# mrShark_10.net
KiCad netlist of a schematic drawn in EAGLE
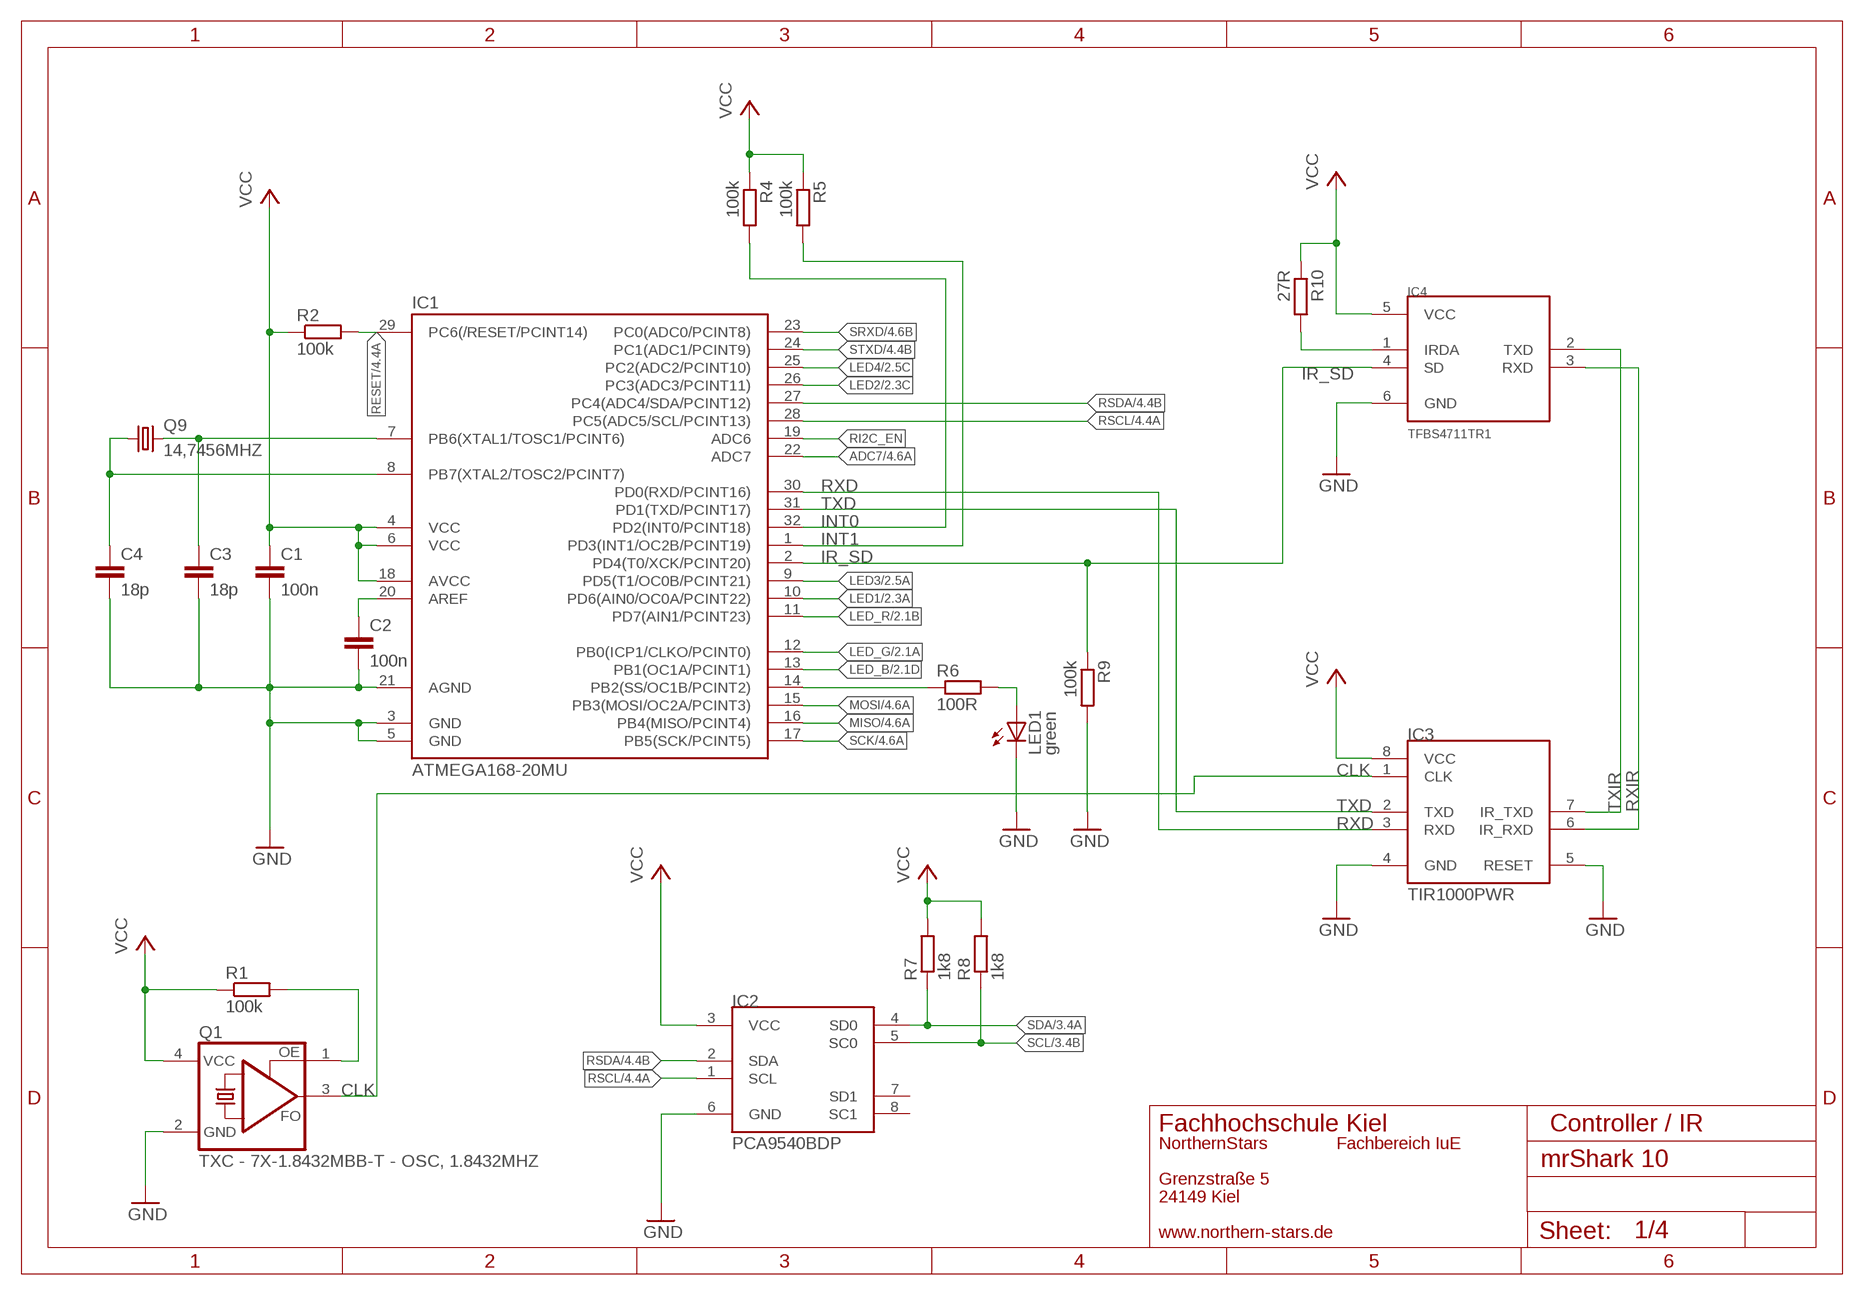
[diagram p0: schematic, sheet 1]
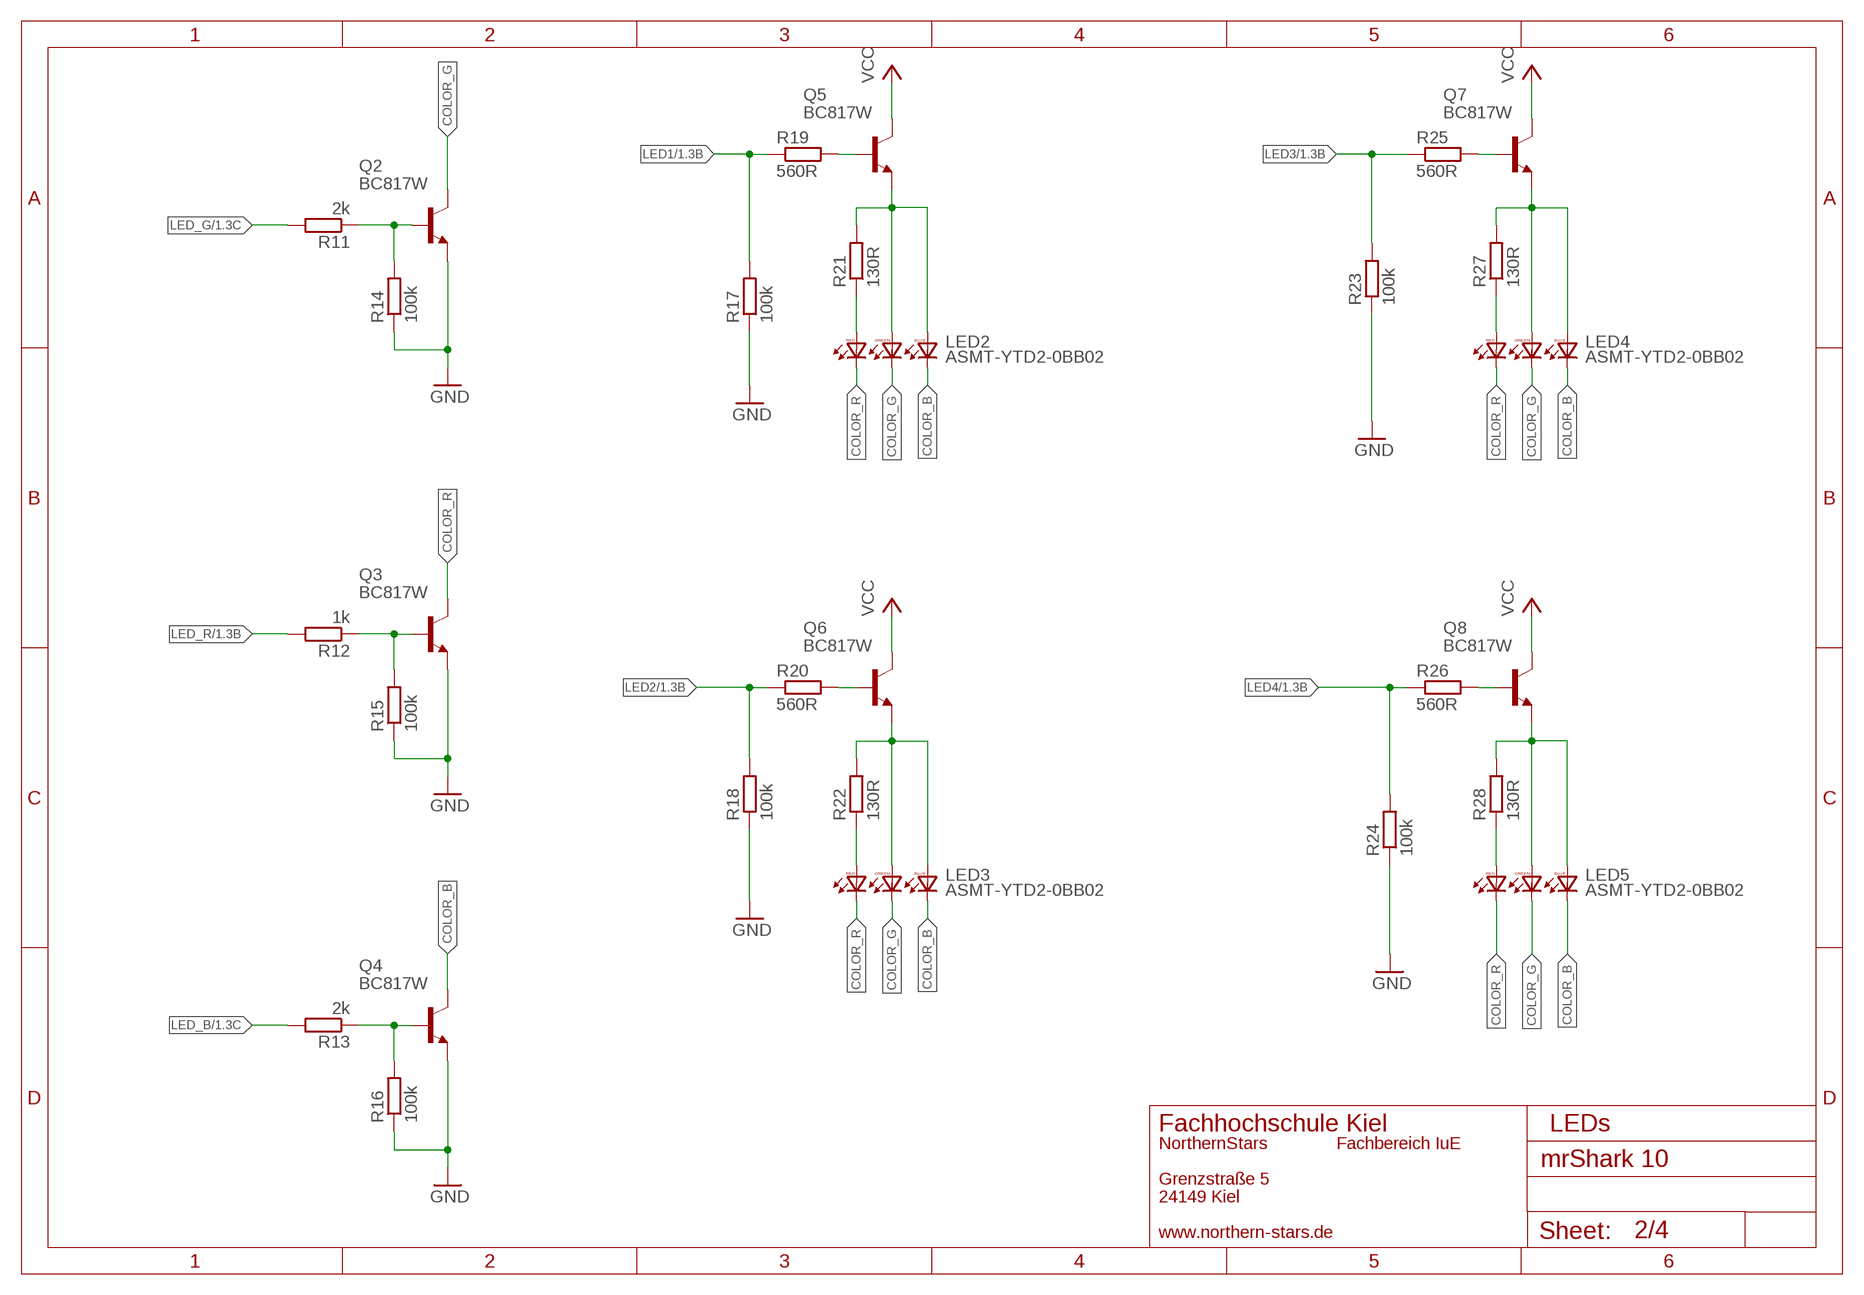
[diagram p1: schematic, sheet 2]
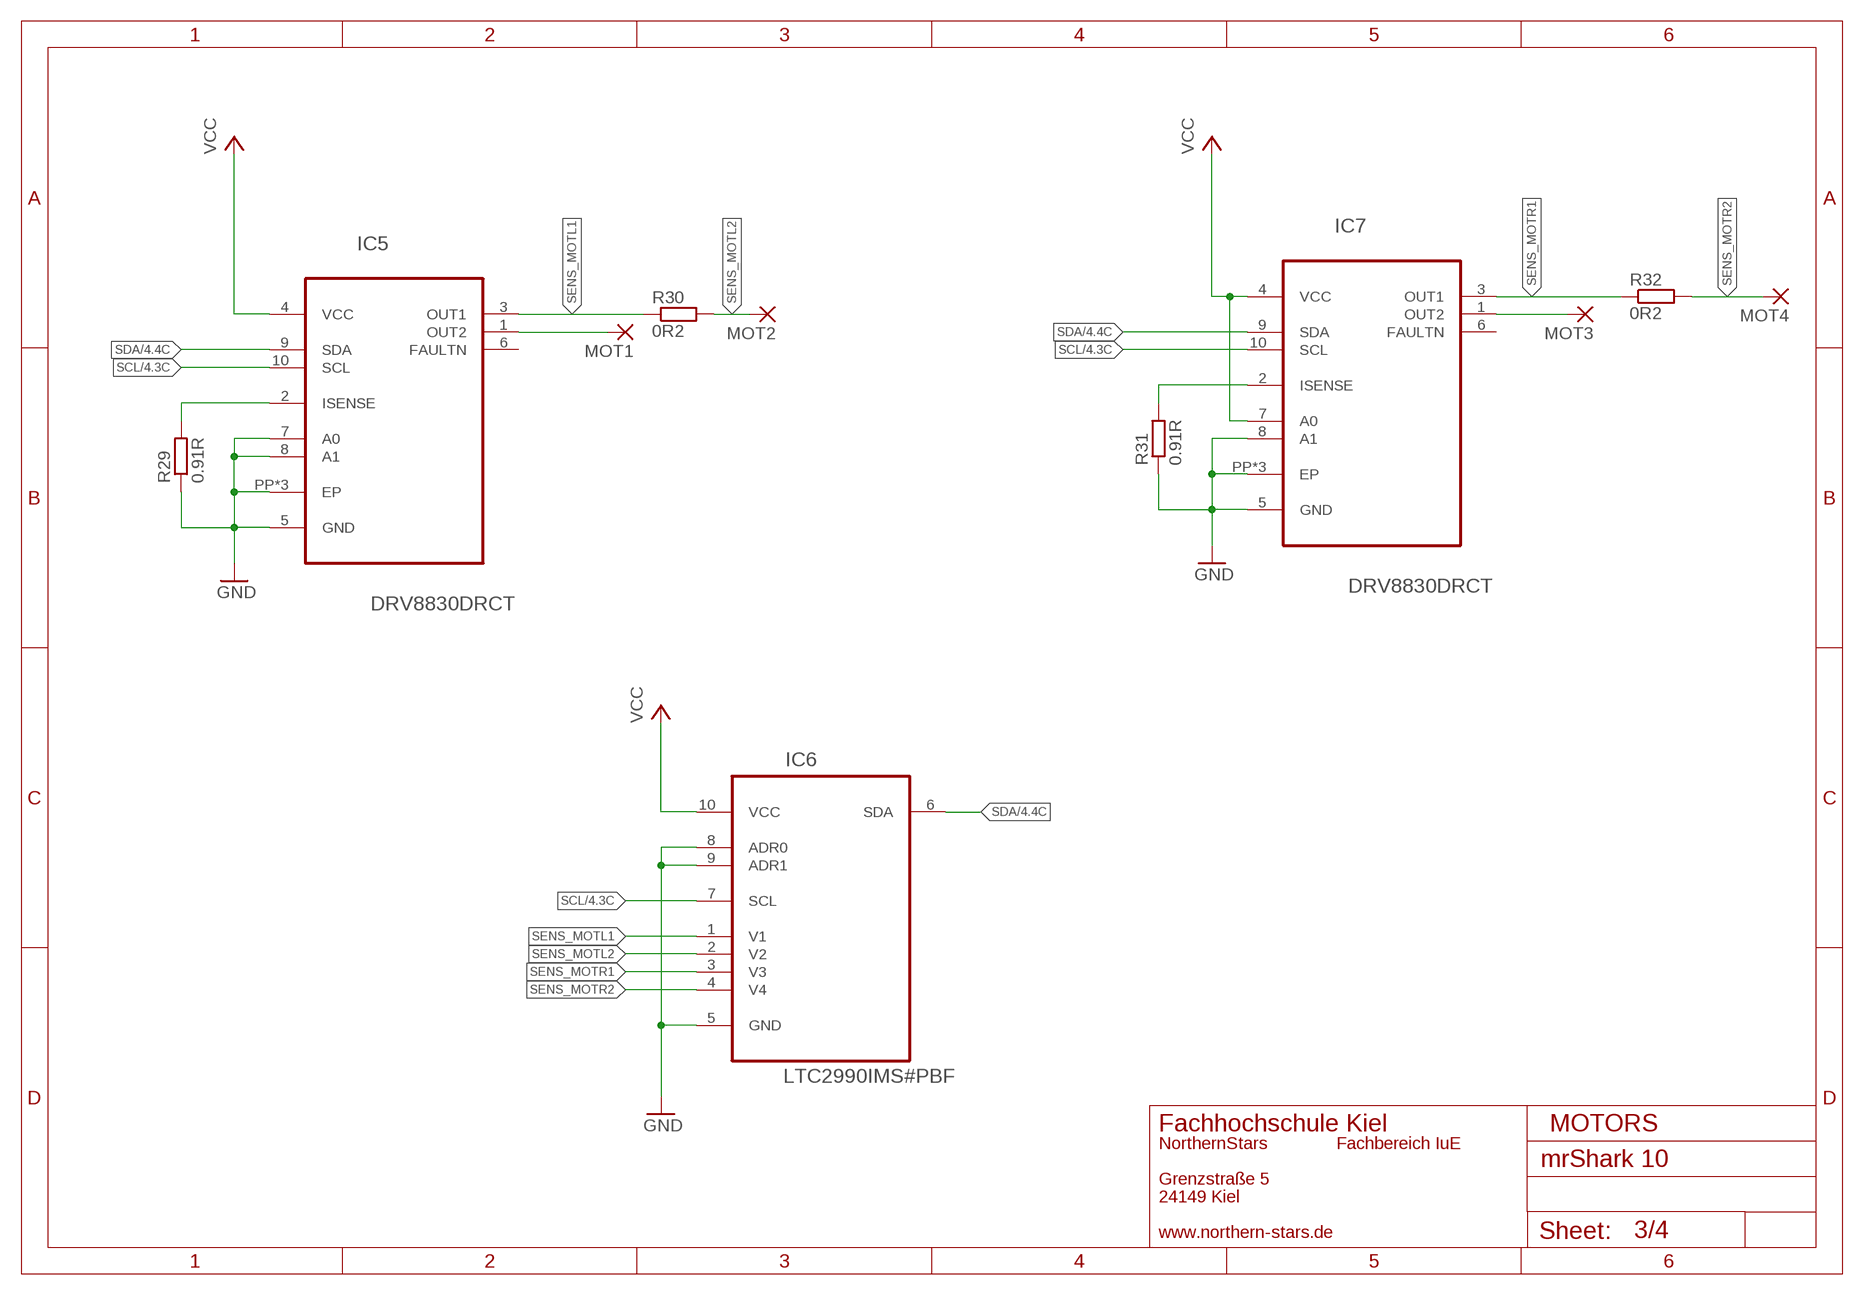
[diagram p2: schematic, sheet 3]
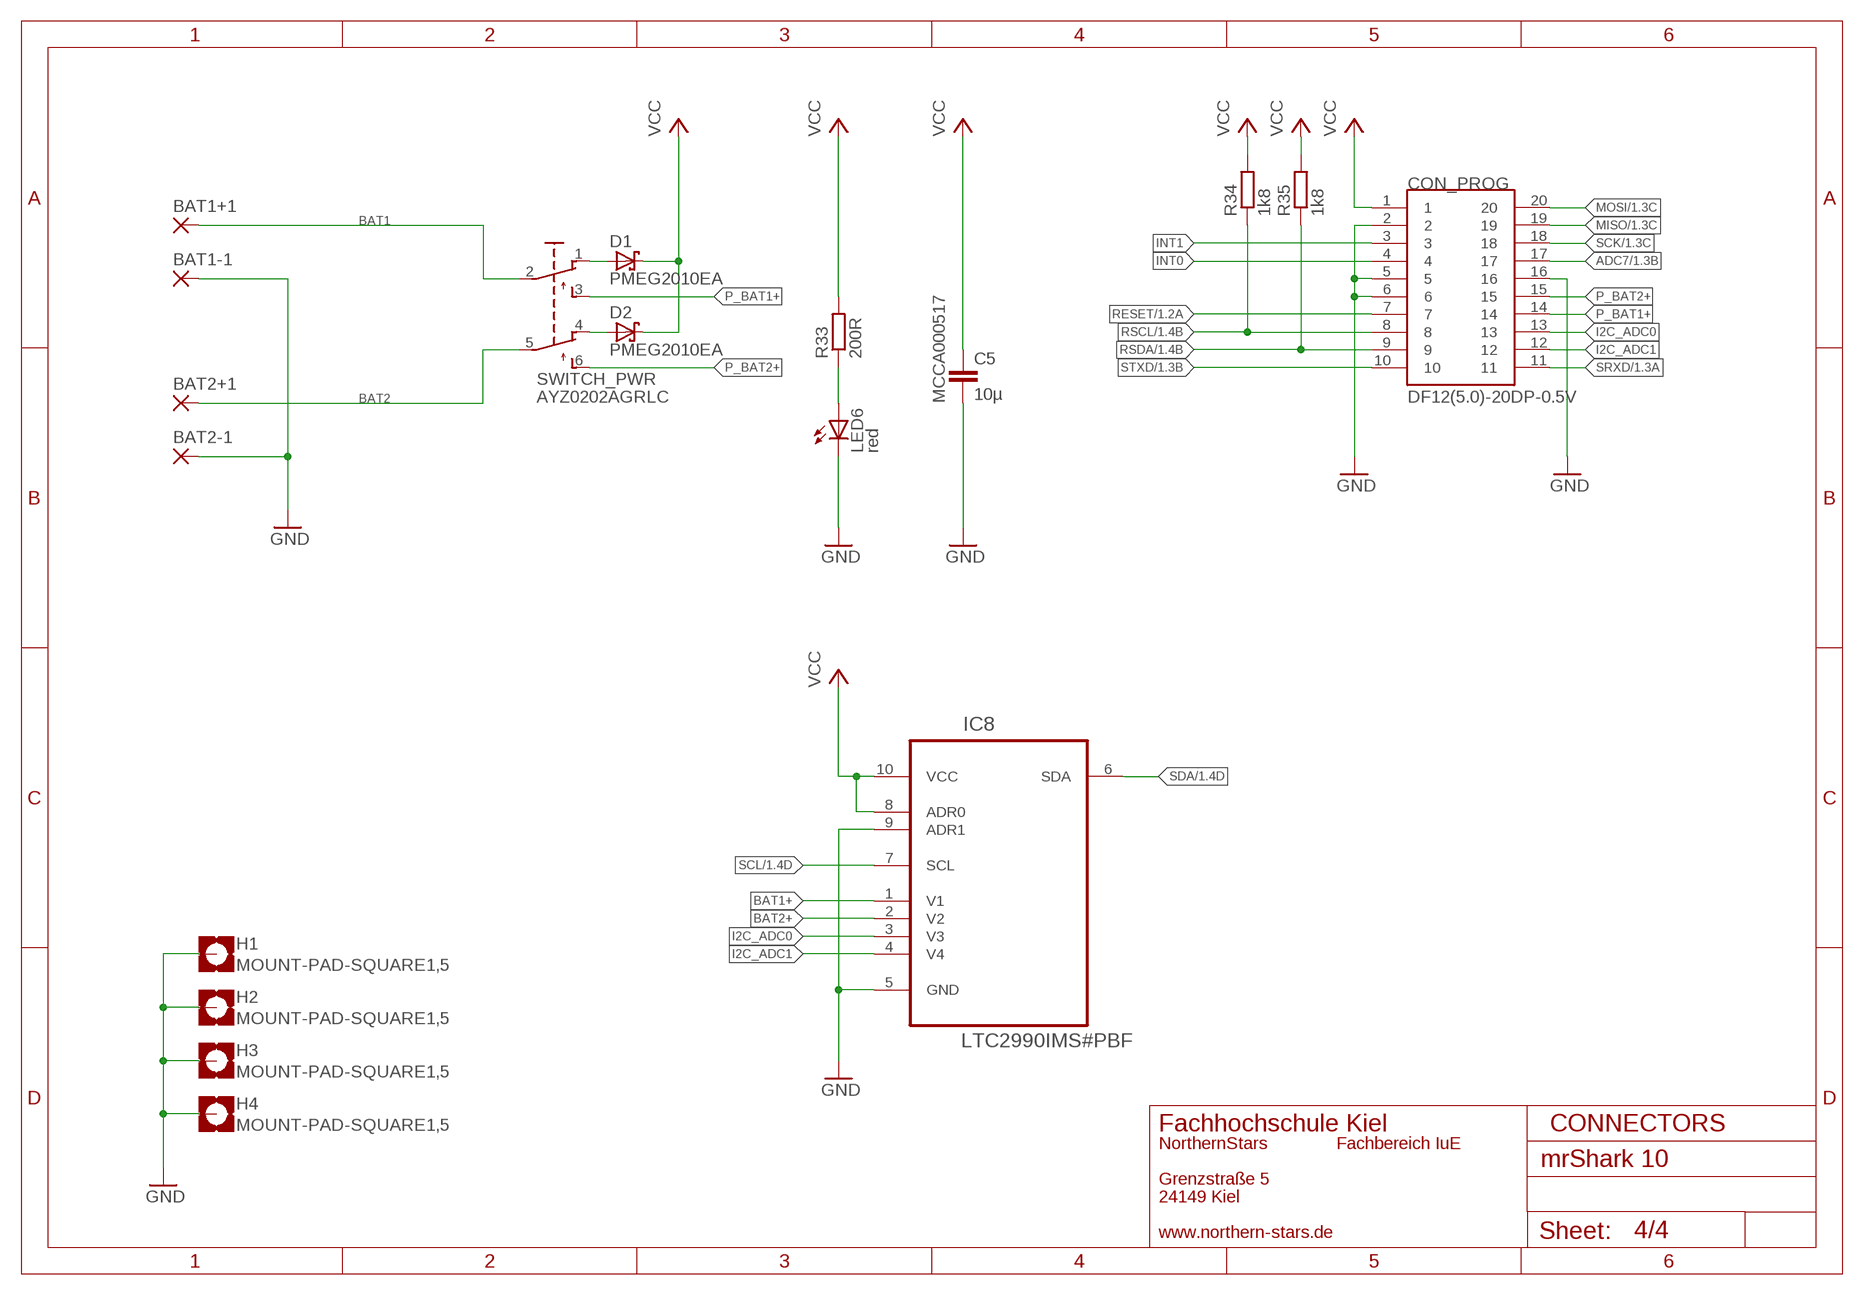
[diagram p3: schematic, sheet 4]

(export (version "E")
  (design (tool "Eeschema 10.0.6"))
  (components
    (comp (ref "C1")
      (value "100n")
      (footprint "eagle-import:C0201")
      (libsource (lib "eagle-import") (part "C-EUC0201"))
    )
    (comp (ref "C2")
      (value "100n")
      (footprint "eagle-import:C0201")
      (libsource (lib "eagle-import") (part "C-EUC0201"))
    )
    (comp (ref "C3")
      (value "18p")
      (footprint "eagle-import:C0201")
      (libsource (lib "eagle-import") (part "C-EUC0201"))
    )
    (comp (ref "C4")
      (value "18p")
      (footprint "eagle-import:C0201")
      (libsource (lib "eagle-import") (part "C-EUC0201"))
    )
    (comp (ref "IC1")
      (value "ATMEGA168-20MU")
      (footprint "eagle-import:MLF32")
      (libsource (lib "eagle-import") (part "ATMEGA48/88/168-MU"))
    )
    (comp (ref "IC2")
      (value "PCA9540BDP")
      (footprint "eagle-import:TSSOP8")
      (libsource (lib "eagle-import") (part "PCA9540TSSOP8"))
    )
    (comp (ref "IC3")
      (value "TIR1000PWR")
      (footprint "eagle-import:PW_R-PDSO-G08")
      (libsource (lib "eagle-import") (part "TIR1000PWR"))
    )
    (comp (ref "IC4")
      (value "TFBS4711TR1")
      (footprint "eagle-import:TFBS4711")
      (libsource (lib "eagle-import") (part "TFBS4711TR1"))
    )
    (comp (ref "LED1")
      (value "green")
      (footprint "eagle-import:CHIPLED_0603")
      (libsource (lib "eagle-import") (part "LEDCHIPLED_0603"))
    )
    (comp (ref "Q1")
      (value "TXC - 7X-1.8432MBB-T - OSC, 1.8432MHZ")
      (footprint "eagle-import:3.2X2.5")
      (libsource (lib "eagle-import") (part "7X-SERIES"))
    )
    (comp (ref "Q9")
      (value "14,7456MHZ")
      (footprint "eagle-import:TXC_7B_SERIES")
      (libsource (lib "eagle-import") (part "TXC-7B-SERIESSMD"))
    )
    (comp (ref "R1")
      (value "100k")
      (footprint "eagle-import:R0201")
      (libsource (lib "eagle-import") (part "R-EU_R0201"))
    )
    (comp (ref "R2")
      (value "100k")
      (footprint "eagle-import:R0201")
      (libsource (lib "eagle-import") (part "R-EU_R0201"))
    )
    (comp (ref "R4")
      (value "100k")
      (footprint "eagle-import:R0201")
      (libsource (lib "eagle-import") (part "R-EU_R0201"))
    )
    (comp (ref "R5")
      (value "100k")
      (footprint "eagle-import:R0201")
      (libsource (lib "eagle-import") (part "R-EU_R0201"))
    )
    (comp (ref "R6")
      (value "100R")
      (footprint "eagle-import:R0201")
      (libsource (lib "eagle-import") (part "R-EU_R0201"))
    )
    (comp (ref "R7")
      (value "1k8")
      (footprint "eagle-import:R0201")
      (libsource (lib "eagle-import") (part "R-EU_R0201"))
    )
    (comp (ref "R8")
      (value "1k8")
      (footprint "eagle-import:R0201")
      (libsource (lib "eagle-import") (part "R-EU_R0201"))
    )
    (comp (ref "R9")
      (value "100k")
      (footprint "eagle-import:R0201")
      (libsource (lib "eagle-import") (part "R-EU_R0201"))
    )
    (comp (ref "R10")
      (value "27R")
      (footprint "eagle-import:R0201")
      (libsource (lib "eagle-import") (part "R-EU_R0201"))
    )
    (comp (ref "IC5")
      (value "DRV8830DRCT")
      (footprint "eagle-import:S-PDSO-N10")
      (libsource (lib "eagle-import") (part "DRV8830DGQRWSON"))
    )
    (comp (ref "IC6")
      (value "LTC2990IMS#PBF")
      (footprint "eagle-import:SOP50P490X110-10N")
      (libsource (lib "eagle-import") (part "LTC2990IMSPBF"))
    )
    (comp (ref "IC7")
      (value "DRV8830DRCT")
      (footprint "eagle-import:S-PDSO-N10")
      (libsource (lib "eagle-import") (part "DRV8830DGQRWSON"))
    )
    (comp (ref "MOT1")
      (value "1,6/0,9")
      (footprint "eagle-import:1,6_0,9")
      (libsource (lib "eagle-import") (part "1,6/0,9"))
    )
    (comp (ref "MOT2")
      (value "1,6/0,9")
      (footprint "eagle-import:1,6_0,9")
      (libsource (lib "eagle-import") (part "1,6/0,9"))
    )
    (comp (ref "MOT3")
      (value "1,6/0,9")
      (footprint "eagle-import:1,6_0,9")
      (libsource (lib "eagle-import") (part "1,6/0,9"))
    )
    (comp (ref "MOT4")
      (value "1,6/0,9")
      (footprint "eagle-import:1,6_0,9")
      (libsource (lib "eagle-import") (part "1,6/0,9"))
    )
    (comp (ref "R29")
      (value "0.91R")
      (footprint "eagle-import:R0603")
      (libsource (lib "eagle-import") (part "R-EU_R0603"))
    )
    (comp (ref "R30")
      (value "0R2")
      (footprint "eagle-import:R0603")
      (libsource (lib "eagle-import") (part "R-EU_R0603"))
    )
    (comp (ref "R31")
      (value "0.91R")
      (footprint "eagle-import:R0603")
      (libsource (lib "eagle-import") (part "R-EU_R0603"))
    )
    (comp (ref "R32")
      (value "0R2")
      (footprint "eagle-import:R0603")
      (libsource (lib "eagle-import") (part "R-EU_R0603"))
    )
    (comp (ref "BAT1+1")
      (value "1,6/0,9")
      (footprint "eagle-import:1,6_0,9")
      (libsource (lib "eagle-import") (part "1,6/0,9"))
    )
    (comp (ref "BAT1-1")
      (value "1,6/0,9")
      (footprint "eagle-import:1,6_0,9")
      (libsource (lib "eagle-import") (part "1,6/0,9"))
    )
    (comp (ref "BAT2+1")
      (value "1,6/0,9")
      (footprint "eagle-import:1,6_0,9")
      (libsource (lib "eagle-import") (part "1,6/0,9"))
    )
    (comp (ref "BAT2-1")
      (value "1,6/0,9")
      (footprint "eagle-import:1,6_0,9")
      (libsource (lib "eagle-import") (part "1,6/0,9"))
    )
    (comp (ref "C5")
      (value "10µ")
      (footprint "eagle-import:C0603K")
      (libsource (lib "eagle-import") (part "C-EUC0603K"))
    )
    (comp (ref "CON_PROG")
      (value "DF12(5.0)-20DP-0.5V")
      (footprint "eagle-import:DF12-20DP")
      (libsource (lib "eagle-import") (part "DF12-20DP"))
    )
    (comp (ref "D1")
      (value "PMEG2010EA")
      (footprint "eagle-import:SOD323-R")
      (libsource (lib "eagle-import") (part "PMEG2010EAR"))
    )
    (comp (ref "D2")
      (value "PMEG2010EA")
      (footprint "eagle-import:SOD323-R")
      (libsource (lib "eagle-import") (part "PMEG2010EAR"))
    )
    (comp (ref "H1")
      (value "MOUNT-PAD-SQUARE1,5")
      (footprint "eagle-import:0,75-PAD-SQUARE")
      (libsource (lib "eagle-import") (part "MOUNT-PAD-SQUARE1,5"))
    )
    (comp (ref "H2")
      (value "MOUNT-PAD-SQUARE1,5")
      (footprint "eagle-import:0,75-PAD-SQUARE")
      (libsource (lib "eagle-import") (part "MOUNT-PAD-SQUARE1,5"))
    )
    (comp (ref "H3")
      (value "MOUNT-PAD-SQUARE1,5")
      (footprint "eagle-import:0,75-PAD-SQUARE")
      (libsource (lib "eagle-import") (part "MOUNT-PAD-SQUARE1,5"))
    )
    (comp (ref "H4")
      (value "MOUNT-PAD-SQUARE1,5")
      (footprint "eagle-import:0,75-PAD-SQUARE")
      (libsource (lib "eagle-import") (part "MOUNT-PAD-SQUARE1,5"))
    )
    (comp (ref "IC8")
      (value "LTC2990IMS#PBF")
      (footprint "eagle-import:SOP50P490X110-10N")
      (libsource (lib "eagle-import") (part "LTC2990IMSPBF"))
    )
    (comp (ref "LED6")
      (value "red")
      (footprint "eagle-import:CHIPLED_0603")
      (libsource (lib "eagle-import") (part "LEDCHIPLED_0603"))
    )
    (comp (ref "R33")
      (value "200R")
      (footprint "eagle-import:R0201")
      (libsource (lib "eagle-import") (part "R-EU_R0201"))
    )
    (comp (ref "R34")
      (value "1k8")
      (footprint "eagle-import:R0201")
      (libsource (lib "eagle-import") (part "R-EU_R0201"))
    )
    (comp (ref "R35")
      (value "1k8")
      (footprint "eagle-import:R0201")
      (libsource (lib "eagle-import") (part "R-EU_R0201"))
    )
    (comp (ref "SWITCH_PWR")
      (value "AYZ0202AGRLC")
      (footprint "eagle-import:AYZ0202AGLRC")
      (libsource (lib "eagle-import") (part "AYZ0202AGRLC"))
    )
    (comp (ref "LED2")
      (value "ASMT-YTD2-0BB02")
      (footprint "eagle-import:PLCC6K")
      (libsource (lib "eagle-import") (part "PLCC6K"))
    )
    (comp (ref "LED3")
      (value "ASMT-YTD2-0BB02")
      (footprint "eagle-import:PLCC6K")
      (libsource (lib "eagle-import") (part "PLCC6K"))
    )
    (comp (ref "LED4")
      (value "ASMT-YTD2-0BB02")
      (footprint "eagle-import:PLCC6K")
      (libsource (lib "eagle-import") (part "PLCC6K"))
    )
    (comp (ref "LED5")
      (value "ASMT-YTD2-0BB02")
      (footprint "eagle-import:PLCC6K")
      (libsource (lib "eagle-import") (part "PLCC6K"))
    )
    (comp (ref "Q2")
      (value "BC817W")
      (footprint "eagle-import:SOT323-BEC")
      (libsource (lib "eagle-import") (part "BC817W"))
    )
    (comp (ref "Q3")
      (value "BC817W")
      (footprint "eagle-import:SOT323-BEC")
      (libsource (lib "eagle-import") (part "BC817W"))
    )
    (comp (ref "Q4")
      (value "BC817W")
      (footprint "eagle-import:SOT323-BEC")
      (libsource (lib "eagle-import") (part "BC817W"))
    )
    (comp (ref "Q5")
      (value "BC817W")
      (footprint "eagle-import:SOT323-BEC")
      (libsource (lib "eagle-import") (part "BC817W"))
    )
    (comp (ref "Q6")
      (value "BC817W")
      (footprint "eagle-import:SOT323-BEC")
      (libsource (lib "eagle-import") (part "BC817W"))
    )
    (comp (ref "Q7")
      (value "BC817W")
      (footprint "eagle-import:SOT323-BEC")
      (libsource (lib "eagle-import") (part "BC817W"))
    )
    (comp (ref "Q8")
      (value "BC817W")
      (footprint "eagle-import:SOT323-BEC")
      (libsource (lib "eagle-import") (part "BC817W"))
    )
    (comp (ref "R11")
      (value "2k")
      (footprint "eagle-import:R0201")
      (libsource (lib "eagle-import") (part "R-EU_R0201"))
    )
    (comp (ref "R12")
      (value "1k")
      (footprint "eagle-import:R0201")
      (libsource (lib "eagle-import") (part "R-EU_R0201"))
    )
    (comp (ref "R13")
      (value "2k")
      (footprint "eagle-import:R0201")
      (libsource (lib "eagle-import") (part "R-EU_R0201"))
    )
    (comp (ref "R14")
      (value "100k")
      (footprint "eagle-import:R0201")
      (libsource (lib "eagle-import") (part "R-EU_R0201"))
    )
    (comp (ref "R15")
      (value "100k")
      (footprint "eagle-import:R0201")
      (libsource (lib "eagle-import") (part "R-EU_R0201"))
    )
    (comp (ref "R16")
      (value "100k")
      (footprint "eagle-import:R0201")
      (libsource (lib "eagle-import") (part "R-EU_R0201"))
    )
    (comp (ref "R17")
      (value "100k")
      (footprint "eagle-import:R0201")
      (libsource (lib "eagle-import") (part "R-EU_R0201"))
    )
    (comp (ref "R18")
      (value "100k")
      (footprint "eagle-import:R0201")
      (libsource (lib "eagle-import") (part "R-EU_R0201"))
    )
    (comp (ref "R19")
      (value "560R")
      (footprint "eagle-import:R0201")
      (libsource (lib "eagle-import") (part "R-EU_R0201"))
    )
    (comp (ref "R20")
      (value "560R")
      (footprint "eagle-import:R0201")
      (libsource (lib "eagle-import") (part "R-EU_R0201"))
    )
    (comp (ref "R21")
      (value "130R")
      (footprint "eagle-import:R0201")
      (libsource (lib "eagle-import") (part "R-EU_R0201"))
    )
    (comp (ref "R22")
      (value "130R")
      (footprint "eagle-import:R0201")
      (libsource (lib "eagle-import") (part "R-EU_R0201"))
    )
    (comp (ref "R23")
      (value "100k")
      (footprint "eagle-import:R0201")
      (libsource (lib "eagle-import") (part "R-EU_R0201"))
    )
    (comp (ref "R24")
      (value "100k")
      (footprint "eagle-import:R0201")
      (libsource (lib "eagle-import") (part "R-EU_R0201"))
    )
    (comp (ref "R25")
      (value "560R")
      (footprint "eagle-import:R0201")
      (libsource (lib "eagle-import") (part "R-EU_R0201"))
    )
    (comp (ref "R26")
      (value "560R")
      (footprint "eagle-import:R0201")
      (libsource (lib "eagle-import") (part "R-EU_R0201"))
    )
    (comp (ref "R27")
      (value "130R")
      (footprint "eagle-import:R0201")
      (libsource (lib "eagle-import") (part "R-EU_R0201"))
    )
    (comp (ref "R28")
      (value "130R")
      (footprint "eagle-import:R0201")
      (libsource (lib "eagle-import") (part "R-EU_R0201"))
    )
  )
  (nets
    (net (code "1") (name "ADC7") (class "Default")
      (node (ref "CON_PROG") (pin "17") (pinfunction "17_17") (pintype "bidirectional"))
      (node (ref "IC1") (pin "22") (pinfunction "ADC7_22") (pintype "passive"))
    )
    (net (code "2") (name "BAT1") (class "Default")
      (node (ref "BAT1+1") (pin "1") (pinfunction "P_1") (pintype "passive"))
      (node (ref "SWITCH_PWR") (pin "2") (pinfunction "P_2") (pintype "passive"))
    )
    (net (code "3") (name "BAT1+") (class "Default")
      (node (ref "D1") (pin "A") (pinfunction "A_A") (pintype "passive"))
      (node (ref "IC8") (pin "1") (pinfunction "V1_1") (pintype "input"))
      (node (ref "SWITCH_PWR") (pin "1") (pinfunction "O_1") (pintype "passive"))
    )
    (net (code "4") (name "BAT2") (class "Default")
      (node (ref "BAT2+1") (pin "1") (pinfunction "P_1") (pintype "passive"))
      (node (ref "SWITCH_PWR") (pin "5") (pinfunction "P1_5") (pintype "passive"))
    )
    (net (code "5") (name "BAT2+") (class "Default")
      (node (ref "D2") (pin "A") (pinfunction "A_A") (pintype "passive"))
      (node (ref "IC8") (pin "2") (pinfunction "V2_2") (pintype "input"))
      (node (ref "SWITCH_PWR") (pin "4") (pinfunction "O1_4") (pintype "passive"))
    )
    (net (code "6") (name "CLK") (class "Default")
      (node (ref "IC3") (pin "1") (pinfunction "CLK_1") (pintype "bidirectional"))
      (node (ref "Q1") (pin "3") (pinfunction "FO_3") (pintype "output"))
    )
    (net (code "7") (name "COLOR_B") (class "Default")
      (node (ref "LED2") (pin "1") (pinfunction "BC_1") (pintype "passive"))
      (node (ref "LED3") (pin "1") (pinfunction "BC_1") (pintype "passive"))
      (node (ref "LED4") (pin "1") (pinfunction "BC_1") (pintype "passive"))
      (node (ref "LED5") (pin "1") (pinfunction "BC_1") (pintype "passive"))
      (node (ref "Q4") (pin "C") (pinfunction "C_C") (pintype "passive"))
    )
    (net (code "8") (name "COLOR_G") (class "Default")
      (node (ref "LED2") (pin "2") (pinfunction "GC_2") (pintype "passive"))
      (node (ref "LED3") (pin "2") (pinfunction "GC_2") (pintype "passive"))
      (node (ref "LED4") (pin "2") (pinfunction "GC_2") (pintype "passive"))
      (node (ref "LED5") (pin "2") (pinfunction "GC_2") (pintype "passive"))
      (node (ref "Q2") (pin "C") (pinfunction "C_C") (pintype "passive"))
    )
    (net (code "9") (name "COLOR_R") (class "Default")
      (node (ref "LED2") (pin "3") (pinfunction "RC_3") (pintype "passive"))
      (node (ref "LED3") (pin "3") (pinfunction "RC_3") (pintype "passive"))
      (node (ref "LED4") (pin "3") (pinfunction "RC_3") (pintype "passive"))
      (node (ref "LED5") (pin "3") (pinfunction "RC_3") (pintype "passive"))
      (node (ref "Q3") (pin "C") (pinfunction "C_C") (pintype "passive"))
    )
    (net (code "10") (name "GND") (class "Default")
      (node (ref "BAT1-1") (pin "1") (pinfunction "P_1") (pintype "passive"))
      (node (ref "BAT2-1") (pin "1") (pinfunction "P_1") (pintype "passive"))
      (node (ref "C1") (pin "2") (pinfunction "2_2") (pintype "passive"))
      (node (ref "C2") (pin "2") (pinfunction "2_2") (pintype "passive"))
      (node (ref "C3") (pin "2") (pinfunction "2_2") (pintype "passive"))
      (node (ref "C4") (pin "2") (pinfunction "2_2") (pintype "passive"))
      (node (ref "C5") (pin "2") (pinfunction "2_2") (pintype "passive"))
      (node (ref "CON_PROG") (pin "16") (pinfunction "16_16") (pintype "bidirectional"))
      (node (ref "CON_PROG") (pin "2") (pinfunction "2_2") (pintype "bidirectional"))
      (node (ref "CON_PROG") (pin "5") (pinfunction "5_5") (pintype "bidirectional"))
      (node (ref "CON_PROG") (pin "6") (pinfunction "6_6") (pintype "bidirectional"))
      (node (ref "H1") (pin "P") (pinfunction "MOUNT_P") (pintype "passive"))
      (node (ref "H2") (pin "P") (pinfunction "MOUNT_P") (pintype "passive"))
      (node (ref "H3") (pin "P") (pinfunction "MOUNT_P") (pintype "passive"))
      (node (ref "H4") (pin "P") (pinfunction "MOUNT_P") (pintype "passive"))
      (node (ref "IC1") (pin "21") (pinfunction "AGND_21") (pintype "power_in"))
      (node (ref "IC1") (pin "3") (pinfunction "GND_3") (pintype "power_in"))
      (node (ref "IC1") (pin "5") (pinfunction "GND_5") (pintype "power_in"))
      (node (ref "IC2") (pin "6") (pinfunction "GND_6") (pintype "bidirectional"))
      (node (ref "IC3") (pin "4") (pinfunction "GND_4") (pintype "bidirectional"))
      (node (ref "IC3") (pin "5") (pinfunction "RESET_5") (pintype "bidirectional"))
      (node (ref "IC4") (pin "6") (pinfunction "GND_6") (pintype "bidirectional"))
      (node (ref "IC5") (pin "5") (pinfunction "GND_5") (pintype "passive"))
      (node (ref "IC5") (pin "7") (pinfunction "A0_7") (pintype "input"))
      (node (ref "IC5") (pin "8") (pinfunction "A1_8") (pintype "input"))
      (node (ref "IC5") (pin "PP") (pinfunction "EP_PP") (pintype "passive"))
      (node (ref "IC5") (pin "PP@1") (pinfunction "EP_PP@1") (pintype "passive"))
      (node (ref "IC5") (pin "PP@2") (pinfunction "EP_PP@2") (pintype "passive"))
      (node (ref "IC6") (pin "5") (pinfunction "GND_5") (pintype "passive"))
      (node (ref "IC6") (pin "8") (pinfunction "ADR0_8") (pintype "input"))
      (node (ref "IC6") (pin "9") (pinfunction "ADR1_9") (pintype "input"))
      (node (ref "IC7") (pin "5") (pinfunction "GND_5") (pintype "passive"))
      (node (ref "IC7") (pin "8") (pinfunction "A1_8") (pintype "input"))
      (node (ref "IC7") (pin "PP") (pinfunction "EP_PP") (pintype "passive"))
      (node (ref "IC7") (pin "PP@1") (pinfunction "EP_PP@1") (pintype "passive"))
      (node (ref "IC7") (pin "PP@2") (pinfunction "EP_PP@2") (pintype "passive"))
      (node (ref "IC8") (pin "5") (pinfunction "GND_5") (pintype "passive"))
      (node (ref "IC8") (pin "9") (pinfunction "ADR1_9") (pintype "input"))
      (node (ref "LED1") (pin "C") (pinfunction "C_C") (pintype "passive"))
      (node (ref "LED6") (pin "C") (pinfunction "C_C") (pintype "passive"))
      (node (ref "Q1") (pin "2") (pinfunction "GND_2") (pintype "power_in"))
      (node (ref "Q2") (pin "E") (pinfunction "E_E") (pintype "passive"))
      (node (ref "Q3") (pin "E") (pinfunction "E_E") (pintype "passive"))
      (node (ref "Q4") (pin "E") (pinfunction "E_E") (pintype "passive"))
      (node (ref "R14") (pin "1") (pinfunction "1_1") (pintype "passive"))
      (node (ref "R15") (pin "1") (pinfunction "1_1") (pintype "passive"))
      (node (ref "R16") (pin "1") (pinfunction "1_1") (pintype "passive"))
      (node (ref "R17") (pin "1") (pinfunction "1_1") (pintype "passive"))
      (node (ref "R18") (pin "1") (pinfunction "1_1") (pintype "passive"))
      (node (ref "R23") (pin "1") (pinfunction "1_1") (pintype "passive"))
      (node (ref "R24") (pin "1") (pinfunction "1_1") (pintype "passive"))
      (node (ref "R29") (pin "1") (pinfunction "1_1") (pintype "passive"))
      (node (ref "R31") (pin "1") (pinfunction "1_1") (pintype "passive"))
      (node (ref "R9") (pin "2") (pinfunction "2_2") (pintype "passive"))
    )
    (net (code "11") (name "I2C_ADC0") (class "Default")
      (node (ref "CON_PROG") (pin "13") (pinfunction "13_13") (pintype "bidirectional"))
      (node (ref "IC8") (pin "3") (pinfunction "V3_3") (pintype "input"))
    )
    (net (code "12") (name "I2C_ADC1") (class "Default")
      (node (ref "CON_PROG") (pin "12") (pinfunction "12_12") (pintype "bidirectional"))
      (node (ref "IC8") (pin "4") (pinfunction "V4_4") (pintype "input"))
    )
    (net (code "13") (name "INT0") (class "Default")
      (node (ref "CON_PROG") (pin "4") (pinfunction "4_4") (pintype "bidirectional"))
      (node (ref "IC1") (pin "32") (pinfunction "PD2(INT0/PCINT18)_32") (pintype "bidirectional"))
      (node (ref "R4") (pin "2") (pinfunction "2_2") (pintype "passive"))
    )
    (net (code "14") (name "INT1") (class "Default")
      (node (ref "CON_PROG") (pin "3") (pinfunction "3_3") (pintype "bidirectional"))
      (node (ref "IC1") (pin "1") (pinfunction "PD3(INT1/OC2B/PCINT19)_1") (pintype "bidirectional"))
      (node (ref "R5") (pin "2") (pinfunction "2_2") (pintype "passive"))
    )
    (net (code "15") (name "IR_SD") (class "Default")
      (node (ref "IC1") (pin "2") (pinfunction "PD4(T0/XCK/PCINT20)_2") (pintype "bidirectional"))
      (node (ref "IC4") (pin "4") (pinfunction "SD_4") (pintype "bidirectional"))
      (node (ref "R9") (pin "1") (pinfunction "1_1") (pintype "passive"))
    )
    (net (code "16") (name "LED1") (class "Default")
      (node (ref "IC1") (pin "10") (pinfunction "PD6(AIN0/OC0A/PCINT22)_10") (pintype "bidirectional"))
      (node (ref "R17") (pin "2") (pinfunction "2_2") (pintype "passive"))
      (node (ref "R19") (pin "1") (pinfunction "1_1") (pintype "passive"))
    )
    (net (code "17") (name "LED2") (class "Default")
      (node (ref "IC1") (pin "26") (pinfunction "PC3(ADC3/PCINT11)_26") (pintype "bidirectional"))
      (node (ref "R18") (pin "2") (pinfunction "2_2") (pintype "passive"))
      (node (ref "R20") (pin "1") (pinfunction "1_1") (pintype "passive"))
    )
    (net (code "18") (name "LED3") (class "Default")
      (node (ref "IC1") (pin "9") (pinfunction "PD5(T1/OC0B/PCINT21)_9") (pintype "bidirectional"))
      (node (ref "R23") (pin "2") (pinfunction "2_2") (pintype "passive"))
      (node (ref "R25") (pin "1") (pinfunction "1_1") (pintype "passive"))
    )
    (net (code "19") (name "LED4") (class "Default")
      (node (ref "IC1") (pin "25") (pinfunction "PC2(ADC2/PCINT10)_25") (pintype "bidirectional"))
      (node (ref "R24") (pin "2") (pinfunction "2_2") (pintype "passive"))
      (node (ref "R26") (pin "1") (pinfunction "1_1") (pintype "passive"))
    )
    (net (code "20") (name "LED_B") (class "Default")
      (node (ref "IC1") (pin "13") (pinfunction "PB1(OC1A/PCINT1)_13") (pintype "bidirectional"))
      (node (ref "R13") (pin "2") (pinfunction "2_2") (pintype "passive"))
    )
    (net (code "21") (name "LED_G") (class "Default")
      (node (ref "IC1") (pin "12") (pinfunction "PB0(ICP1/CLKO/PCINT0)_12") (pintype "bidirectional"))
      (node (ref "R11") (pin "2") (pinfunction "2_2") (pintype "passive"))
    )
    (net (code "22") (name "LED_R") (class "Default")
      (node (ref "IC1") (pin "11") (pinfunction "PD7(AIN1/PCINT23)_11") (pintype "bidirectional"))
      (node (ref "R12") (pin "2") (pinfunction "2_2") (pintype "passive"))
    )
    (net (code "23") (name "MISO") (class "Default")
      (node (ref "CON_PROG") (pin "19") (pinfunction "19_19") (pintype "bidirectional"))
      (node (ref "IC1") (pin "16") (pinfunction "PB4(MISO/PCINT4)_16") (pintype "bidirectional"))
    )
    (net (code "24") (name "MOSI") (class "Default")
      (node (ref "CON_PROG") (pin "20") (pinfunction "20_20") (pintype "bidirectional"))
      (node (ref "IC1") (pin "15") (pinfunction "PB3(MOSI/OC2A/PCINT3)_15") (pintype "bidirectional"))
    )
    (net (code "25") (name "Net-(IC1-AREF)") (class "Default")
      (node (ref "C2") (pin "1") (pinfunction "1_1") (pintype "passive"))
      (node (ref "IC1") (pin "20") (pinfunction "AREF_20") (pintype "passive"))
    )
    (net (code "26") (name "Net-(IC1-PB2(SS{slash}OC1B{slash}PCINT2))") (class "Default")
      (node (ref "IC1") (pin "14") (pinfunction "PB2(SS/OC1B/PCINT2)_14") (pintype "bidirectional"))
      (node (ref "R6") (pin "1") (pinfunction "1_1") (pintype "passive"))
    )
    (net (code "27") (name "Net-(IC1-PB6(XTAL1{slash}TOSC1{slash}PCINT6))") (class "Default")
      (node (ref "C3") (pin "1") (pinfunction "1_1") (pintype "passive"))
      (node (ref "IC1") (pin "7") (pinfunction "PB6(XTAL1/TOSC1/PCINT6)_7") (pintype "bidirectional"))
      (node (ref "Q9") (pin "3") (pinfunction "2_3") (pintype "passive"))
    )
    (net (code "28") (name "Net-(IC1-PB7(XTAL2{slash}TOSC2{slash}PCINT7))") (class "Default")
      (node (ref "C4") (pin "1") (pinfunction "1_1") (pintype "passive"))
      (node (ref "IC1") (pin "8") (pinfunction "PB7(XTAL2/TOSC2/PCINT7)_8") (pintype "bidirectional"))
      (node (ref "Q9") (pin "1") (pinfunction "1_1") (pintype "passive"))
    )
    (net (code "29") (name "Net-(IC4-IRDA)") (class "Default")
      (node (ref "IC4") (pin "1") (pinfunction "IRDA_1") (pintype "bidirectional"))
      (node (ref "R10") (pin "2") (pinfunction "2_2") (pintype "passive"))
    )
    (net (code "30") (name "Net-(IC5-ISENSE)") (class "Default")
      (node (ref "IC5") (pin "2") (pinfunction "ISENSE_2") (pintype "input"))
      (node (ref "R29") (pin "2") (pinfunction "2_2") (pintype "passive"))
    )
    (net (code "31") (name "Net-(IC5-OUT2)") (class "Default")
      (node (ref "IC5") (pin "1") (pinfunction "OUT2_1") (pintype "output"))
      (node (ref "MOT1") (pin "1") (pinfunction "P_1") (pintype "passive"))
    )
    (net (code "32") (name "Net-(IC7-ISENSE)") (class "Default")
      (node (ref "IC7") (pin "2") (pinfunction "ISENSE_2") (pintype "input"))
      (node (ref "R31") (pin "2") (pinfunction "2_2") (pintype "passive"))
    )
    (net (code "33") (name "Net-(IC7-OUT2)") (class "Default")
      (node (ref "IC7") (pin "1") (pinfunction "OUT2_1") (pintype "output"))
      (node (ref "MOT3") (pin "1") (pinfunction "P_1") (pintype "passive"))
    )
    (net (code "34") (name "Net-(LED1-PadA)") (class "Default")
      (node (ref "LED1") (pin "A") (pinfunction "A_A") (pintype "passive"))
      (node (ref "R6") (pin "2") (pinfunction "2_2") (pintype "passive"))
    )
    (net (code "35") (name "Net-(LED2-BA)") (class "Default")
      (node (ref "LED2") (pin "5") (pinfunction "GA_5") (pintype "passive"))
      (node (ref "LED2") (pin "6") (pinfunction "BA_6") (pintype "passive"))
      (node (ref "Q5") (pin "E") (pinfunction "E_E") (pintype "passive"))
      (node (ref "R21") (pin "2") (pinfunction "2_2") (pintype "passive"))
    )
    (net (code "36") (name "Net-(LED2-RA)") (class "Default")
      (node (ref "LED2") (pin "4") (pinfunction "RA_4") (pintype "passive"))
      (node (ref "R21") (pin "1") (pinfunction "1_1") (pintype "passive"))
    )
    (net (code "37") (name "Net-(LED3-BA)") (class "Default")
      (node (ref "LED3") (pin "5") (pinfunction "GA_5") (pintype "passive"))
      (node (ref "LED3") (pin "6") (pinfunction "BA_6") (pintype "passive"))
      (node (ref "Q6") (pin "E") (pinfunction "E_E") (pintype "passive"))
      (node (ref "R22") (pin "2") (pinfunction "2_2") (pintype "passive"))
    )
    (net (code "38") (name "Net-(LED3-RA)") (class "Default")
      (node (ref "LED3") (pin "4") (pinfunction "RA_4") (pintype "passive"))
      (node (ref "R22") (pin "1") (pinfunction "1_1") (pintype "passive"))
    )
    (net (code "39") (name "Net-(LED4-BA)") (class "Default")
      (node (ref "LED4") (pin "5") (pinfunction "GA_5") (pintype "passive"))
      (node (ref "LED4") (pin "6") (pinfunction "BA_6") (pintype "passive"))
      (node (ref "Q7") (pin "E") (pinfunction "E_E") (pintype "passive"))
      (node (ref "R27") (pin "2") (pinfunction "2_2") (pintype "passive"))
    )
    (net (code "40") (name "Net-(LED4-RA)") (class "Default")
      (node (ref "LED4") (pin "4") (pinfunction "RA_4") (pintype "passive"))
      (node (ref "R27") (pin "1") (pinfunction "1_1") (pintype "passive"))
    )
    (net (code "41") (name "Net-(LED5-BA)") (class "Default")
      (node (ref "LED5") (pin "5") (pinfunction "GA_5") (pintype "passive"))
      (node (ref "LED5") (pin "6") (pinfunction "BA_6") (pintype "passive"))
      (node (ref "Q8") (pin "E") (pinfunction "E_E") (pintype "passive"))
      (node (ref "R28") (pin "2") (pinfunction "2_2") (pintype "passive"))
    )
    (net (code "42") (name "Net-(LED5-RA)") (class "Default")
      (node (ref "LED5") (pin "4") (pinfunction "RA_4") (pintype "passive"))
      (node (ref "R28") (pin "1") (pinfunction "1_1") (pintype "passive"))
    )
    (net (code "43") (name "Net-(LED6-PadA)") (class "Default")
      (node (ref "LED6") (pin "A") (pinfunction "A_A") (pintype "passive"))
      (node (ref "R33") (pin "1") (pinfunction "1_1") (pintype "passive"))
    )
    (net (code "44") (name "Net-(Q1-OE)") (class "Default")
      (node (ref "Q1") (pin "1") (pinfunction "OE_1") (pintype "input"))
      (node (ref "R1") (pin "2") (pinfunction "2_2") (pintype "passive"))
    )
    (net (code "45") (name "Net-(Q2-PadB)") (class "Default")
      (node (ref "Q2") (pin "B") (pinfunction "B_B") (pintype "passive"))
      (node (ref "R11") (pin "1") (pinfunction "1_1") (pintype "passive"))
      (node (ref "R14") (pin "2") (pinfunction "2_2") (pintype "passive"))
    )
    (net (code "46") (name "Net-(Q3-PadB)") (class "Default")
      (node (ref "Q3") (pin "B") (pinfunction "B_B") (pintype "passive"))
      (node (ref "R12") (pin "1") (pinfunction "1_1") (pintype "passive"))
      (node (ref "R15") (pin "2") (pinfunction "2_2") (pintype "passive"))
    )
    (net (code "47") (name "Net-(Q4-PadB)") (class "Default")
      (node (ref "Q4") (pin "B") (pinfunction "B_B") (pintype "passive"))
      (node (ref "R13") (pin "1") (pinfunction "1_1") (pintype "passive"))
      (node (ref "R16") (pin "2") (pinfunction "2_2") (pintype "passive"))
    )
    (net (code "48") (name "Net-(Q5-PadB)") (class "Default")
      (node (ref "Q5") (pin "B") (pinfunction "B_B") (pintype "passive"))
      (node (ref "R19") (pin "2") (pinfunction "2_2") (pintype "passive"))
    )
    (net (code "49") (name "Net-(Q6-PadB)") (class "Default")
      (node (ref "Q6") (pin "B") (pinfunction "B_B") (pintype "passive"))
      (node (ref "R20") (pin "2") (pinfunction "2_2") (pintype "passive"))
    )
    (net (code "50") (name "Net-(Q7-PadB)") (class "Default")
      (node (ref "Q7") (pin "B") (pinfunction "B_B") (pintype "passive"))
      (node (ref "R25") (pin "2") (pinfunction "2_2") (pintype "passive"))
    )
    (net (code "51") (name "Net-(Q8-PadB)") (class "Default")
      (node (ref "Q8") (pin "B") (pinfunction "B_B") (pintype "passive"))
      (node (ref "R26") (pin "2") (pinfunction "2_2") (pintype "passive"))
    )
    (net (code "52") (name "P_BAT1+") (class "Default")
      (node (ref "CON_PROG") (pin "14") (pinfunction "14_14") (pintype "bidirectional"))
      (node (ref "SWITCH_PWR") (pin "3") (pinfunction "S_3") (pintype "passive"))
    )
    (net (code "53") (name "P_BAT2+") (class "Default")
      (node (ref "CON_PROG") (pin "15") (pinfunction "15_15") (pintype "bidirectional"))
      (node (ref "SWITCH_PWR") (pin "6") (pinfunction "S1_6") (pintype "passive"))
    )
    (net (code "54") (name "RESET") (class "Default")
      (node (ref "CON_PROG") (pin "7") (pinfunction "7_7") (pintype "bidirectional"))
      (node (ref "IC1") (pin "29") (pinfunction "PC6(/RESET/PCINT14)_29") (pintype "bidirectional"))
      (node (ref "R2") (pin "2") (pinfunction "2_2") (pintype "passive"))
    )
    (net (code "55") (name "RI2C_EN") (class "Default")
      (node (ref "IC1") (pin "19") (pinfunction "ADC6_19") (pintype "passive"))
    )
    (net (code "56") (name "RSCL") (class "Default")
      (node (ref "CON_PROG") (pin "8") (pinfunction "8_8") (pintype "bidirectional"))
      (node (ref "IC1") (pin "28") (pinfunction "PC5(ADC5/SCL/PCINT13)_28") (pintype "bidirectional"))
      (node (ref "IC2") (pin "1") (pinfunction "SCL_1") (pintype "bidirectional"))
      (node (ref "R34") (pin "1") (pinfunction "1_1") (pintype "passive"))
    )
    (net (code "57") (name "RSDA") (class "Default")
      (node (ref "CON_PROG") (pin "9") (pinfunction "9_9") (pintype "bidirectional"))
      (node (ref "IC1") (pin "27") (pinfunction "PC4(ADC4/SDA/PCINT12)_27") (pintype "bidirectional"))
      (node (ref "IC2") (pin "2") (pinfunction "SDA_2") (pintype "bidirectional"))
      (node (ref "R35") (pin "1") (pinfunction "1_1") (pintype "passive"))
    )
    (net (code "58") (name "RXD") (class "Default")
      (node (ref "IC1") (pin "30") (pinfunction "PD0(RXD/PCINT16)_30") (pintype "bidirectional"))
      (node (ref "IC3") (pin "3") (pinfunction "RXD_3") (pintype "bidirectional"))
    )
    (net (code "59") (name "RXIR") (class "Default")
      (node (ref "IC3") (pin "6") (pinfunction "IR_RXD_6") (pintype "bidirectional"))
      (node (ref "IC4") (pin "3") (pinfunction "RXD_3") (pintype "output"))
    )
    (net (code "60") (name "SCK") (class "Default")
      (node (ref "CON_PROG") (pin "18") (pinfunction "18_18") (pintype "bidirectional"))
      (node (ref "IC1") (pin "17") (pinfunction "PB5(SCK/PCINT5)_17") (pintype "bidirectional"))
    )
    (net (code "61") (name "SCL") (class "Default")
      (node (ref "IC2") (pin "5") (pinfunction "SC0_5") (pintype "bidirectional"))
      (node (ref "IC5") (pin "10") (pinfunction "SCL_10") (pintype "input"))
      (node (ref "IC6") (pin "7") (pinfunction "SCL_7") (pintype "input"))
      (node (ref "IC7") (pin "10") (pinfunction "SCL_10") (pintype "input"))
      (node (ref "IC8") (pin "7") (pinfunction "SCL_7") (pintype "input"))
      (node (ref "R8") (pin "1") (pinfunction "1_1") (pintype "passive"))
    )
    (net (code "62") (name "SDA") (class "Default")
      (node (ref "IC2") (pin "4") (pinfunction "SD0_4") (pintype "bidirectional"))
      (node (ref "IC5") (pin "9") (pinfunction "SDA_9") (pintype "bidirectional"))
      (node (ref "IC6") (pin "6") (pinfunction "SDA_6") (pintype "bidirectional"))
      (node (ref "IC7") (pin "9") (pinfunction "SDA_9") (pintype "bidirectional"))
      (node (ref "IC8") (pin "6") (pinfunction "SDA_6") (pintype "bidirectional"))
      (node (ref "R7") (pin "1") (pinfunction "1_1") (pintype "passive"))
    )
    (net (code "63") (name "SENS_MOTL1") (class "Default")
      (node (ref "IC5") (pin "3") (pinfunction "OUT1_3") (pintype "output"))
      (node (ref "IC6") (pin "1") (pinfunction "V1_1") (pintype "input"))
      (node (ref "R30") (pin "1") (pinfunction "1_1") (pintype "passive"))
    )
    (net (code "64") (name "SENS_MOTL2") (class "Default")
      (node (ref "IC6") (pin "2") (pinfunction "V2_2") (pintype "input"))
      (node (ref "MOT2") (pin "1") (pinfunction "P_1") (pintype "passive"))
      (node (ref "R30") (pin "2") (pinfunction "2_2") (pintype "passive"))
    )
    (net (code "65") (name "SENS_MOTR1") (class "Default")
      (node (ref "IC6") (pin "3") (pinfunction "V3_3") (pintype "input"))
      (node (ref "IC7") (pin "3") (pinfunction "OUT1_3") (pintype "output"))
      (node (ref "R32") (pin "1") (pinfunction "1_1") (pintype "passive"))
    )
    (net (code "66") (name "SENS_MOTR2") (class "Default")
      (node (ref "IC6") (pin "4") (pinfunction "V4_4") (pintype "input"))
      (node (ref "MOT4") (pin "1") (pinfunction "P_1") (pintype "passive"))
      (node (ref "R32") (pin "2") (pinfunction "2_2") (pintype "passive"))
    )
    (net (code "67") (name "SRXD") (class "Default")
      (node (ref "CON_PROG") (pin "11") (pinfunction "11_11") (pintype "bidirectional"))
      (node (ref "IC1") (pin "23") (pinfunction "PC0(ADC0/PCINT8)_23") (pintype "bidirectional"))
    )
    (net (code "68") (name "STXD") (class "Default")
      (node (ref "CON_PROG") (pin "10") (pinfunction "10_10") (pintype "bidirectional"))
      (node (ref "IC1") (pin "24") (pinfunction "PC1(ADC1/PCINT9)_24") (pintype "bidirectional"))
    )
    (net (code "69") (name "TXD") (class "Default")
      (node (ref "IC1") (pin "31") (pinfunction "PD1(TXD/PCINT17)_31") (pintype "bidirectional"))
      (node (ref "IC3") (pin "2") (pinfunction "TXD_2") (pintype "bidirectional"))
    )
    (net (code "70") (name "TXIR") (class "Default")
      (node (ref "IC3") (pin "7") (pinfunction "IR_TXD_7") (pintype "bidirectional"))
      (node (ref "IC4") (pin "2") (pinfunction "TXD_2") (pintype "input"))
    )
    (net (code "71") (name "VCC") (class "Default")
      (node (ref "C1") (pin "1") (pinfunction "1_1") (pintype "passive"))
      (node (ref "C5") (pin "1") (pinfunction "1_1") (pintype "passive"))
      (node (ref "CON_PROG") (pin "1") (pinfunction "1_1") (pintype "bidirectional"))
      (node (ref "D1") (pin "C") (pinfunction "C_C") (pintype "passive"))
      (node (ref "D2") (pin "C") (pinfunction "C_C") (pintype "passive"))
      (node (ref "IC1") (pin "18") (pinfunction "AVCC_18") (pintype "passive"))
      (node (ref "IC1") (pin "4") (pinfunction "VCC_4") (pintype "power_in"))
      (node (ref "IC1") (pin "6") (pinfunction "VCC_6") (pintype "power_in"))
      (node (ref "IC2") (pin "3") (pinfunction "VCC_3") (pintype "bidirectional"))
      (node (ref "IC3") (pin "8") (pinfunction "VCC_8") (pintype "bidirectional"))
      (node (ref "IC4") (pin "5") (pinfunction "VCC_5") (pintype "power_in"))
      (node (ref "IC5") (pin "4") (pinfunction "VCC_4") (pintype "power_in"))
      (node (ref "IC6") (pin "10") (pinfunction "VCC_10") (pintype "power_in"))
      (node (ref "IC7") (pin "4") (pinfunction "VCC_4") (pintype "power_in"))
      (node (ref "IC7") (pin "7") (pinfunction "A0_7") (pintype "input"))
      (node (ref "IC8") (pin "10") (pinfunction "VCC_10") (pintype "power_in"))
      (node (ref "IC8") (pin "8") (pinfunction "ADR0_8") (pintype "input"))
      (node (ref "Q1") (pin "4") (pinfunction "VCC_4") (pintype "power_in"))
      (node (ref "Q5") (pin "C") (pinfunction "C_C") (pintype "passive"))
      (node (ref "Q6") (pin "C") (pinfunction "C_C") (pintype "passive"))
      (node (ref "Q7") (pin "C") (pinfunction "C_C") (pintype "passive"))
      (node (ref "Q8") (pin "C") (pinfunction "C_C") (pintype "passive"))
      (node (ref "R1") (pin "1") (pinfunction "1_1") (pintype "passive"))
      (node (ref "R10") (pin "1") (pinfunction "1_1") (pintype "passive"))
      (node (ref "R2") (pin "1") (pinfunction "1_1") (pintype "passive"))
      (node (ref "R33") (pin "2") (pinfunction "2_2") (pintype "passive"))
      (node (ref "R34") (pin "2") (pinfunction "2_2") (pintype "passive"))
      (node (ref "R35") (pin "2") (pinfunction "2_2") (pintype "passive"))
      (node (ref "R4") (pin "1") (pinfunction "1_1") (pintype "passive"))
      (node (ref "R5") (pin "1") (pinfunction "1_1") (pintype "passive"))
      (node (ref "R7") (pin "2") (pinfunction "2_2") (pintype "passive"))
      (node (ref "R8") (pin "2") (pinfunction "2_2") (pintype "passive"))
    )
    (net (code "72") (name "unconnected-(IC2-SC1-Pad8)") (class "Default")
      (node (ref "IC2") (pin "8") (pinfunction "SC1_8") (pintype "bidirectional"))
    )
    (net (code "73") (name "unconnected-(IC2-SD1-Pad7)") (class "Default")
      (node (ref "IC2") (pin "7") (pinfunction "SD1_7") (pintype "bidirectional"))
    )
    (net (code "74") (name "unconnected-(IC5-FAULTN-Pad6)") (class "Default")
      (node (ref "IC5") (pin "6") (pinfunction "FAULTN_6") (pintype "output"))
    )
    (net (code "75") (name "unconnected-(IC7-FAULTN-Pad6)") (class "Default")
      (node (ref "IC7") (pin "6") (pinfunction "FAULTN_6") (pintype "output"))
    )
  )
)
